# MCU.net
KiCad netlist of a schematic drawn in Altium Designer
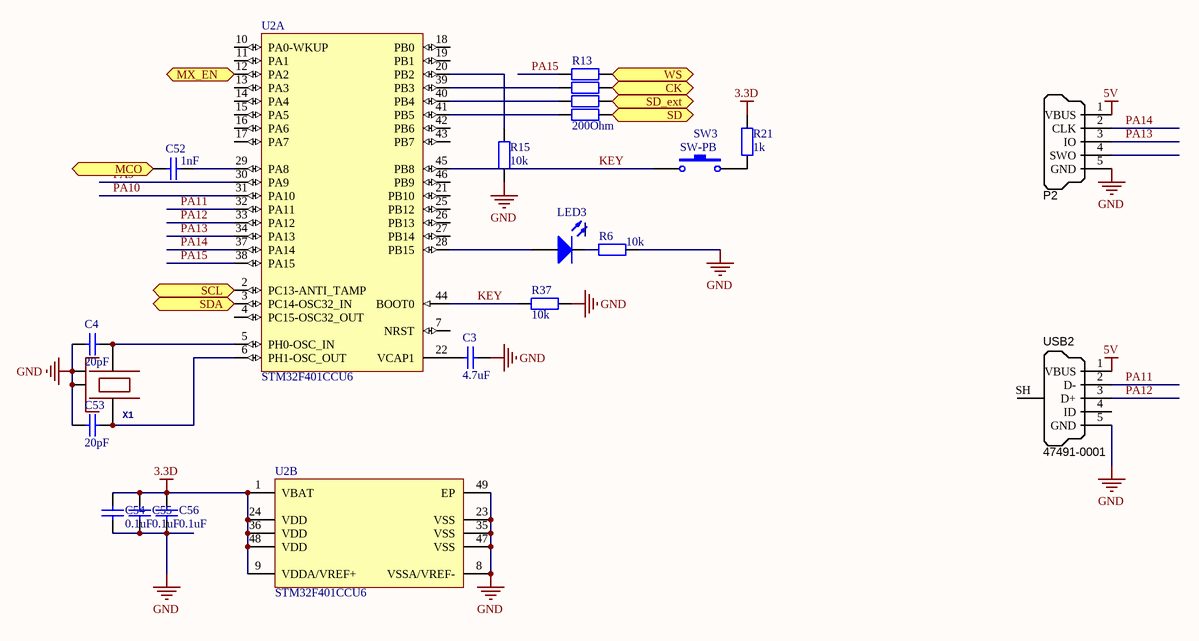
[diagram p0: MCU.SchDoc]

(export (version "E")
  (design (tool "Eeschema 10.0.6"))
  (components
    (comp (ref "C3")
      (value "4.7uF")
      (footprint "0603L")
      (description "Capacitor")
      (fields (field (name "Comment") "Cap") (field (name "PUBLISHER") "Altium Limited"))
      (libsource (lib "RTC6705") (part "Cap"))
    )
    (comp (ref "C4")
      (value "20pF")
      (footprint "0402")
      (description "Capacitor")
      (fields (field (name "Comment") "Cap") (field (name "PUBLISHER") "Altium Limited"))
      (libsource (lib "RTC6705") (part "Cap"))
    )
    (comp (ref "C52")
      (value "1nF")
      (footprint "0402")
      (description "Capacitor")
      (libsource (lib "RTC6705") (part "Cap"))
    )
    (comp (ref "C53")
      (value "20pF")
      (footprint "0402")
      (description "Capacitor")
      (fields (field (name "Comment") "Cap") (field (name "PUBLISHER") "Altium Limited"))
      (libsource (lib "RTC6705") (part "Cap"))
    )
    (comp (ref "C54")
      (value "0.1uF")
      (footprint "0402")
      (description "Capacitor")
      (fields (field (name "Comment") "Cap") (field (name "PUBLISHER") "Altium Limited"))
      (libsource (lib "RTC6705") (part "Cap"))
    )
    (comp (ref "C55")
      (value "0.1uF")
      (footprint "0402")
      (description "Capacitor")
      (fields (field (name "Comment") "Cap") (field (name "PUBLISHER") "Altium Limited"))
      (libsource (lib "RTC6705") (part "Cap"))
    )
    (comp (ref "C56")
      (value "0.1uF")
      (footprint "0402")
      (description "Capacitor")
      (fields (field (name "Comment") "Cap") (field (name "PUBLISHER") "Altium Limited"))
      (libsource (lib "RTC6705") (part "Cap"))
    )
    (comp (ref "LED3")
      (value "LED0")
      (footprint "0603")
      (description "Typical INFRARED GaAs LED")
      (fields (field (name "PUBLISHER") "Altium Limited"))
      (libsource (lib "Miscellaneous Devices") (part "LED0"))
    )
    (comp (ref "P2")
      (value "SWD_MicroUSB")
      (footprint "MICRO-YZX")
      (description "Connector SMD USB Micro Type B middle mount")
      (libsource (lib "sch") (part "SWD_MicroUSB"))
    )
    (comp (ref "R6")
      (value "10k")
      (footprint "0402")
      (description "Resistor")
      (fields (field (name "PUBLISHER") "Altium Limited"))
      (libsource (lib "") (part "Res2_2"))
    )
    (comp (ref "R13")
      (value "200Ohm")
      (footprint "0402X4")
      (description "Resistor")
      (fields (field (name "Comment") "Res*4") (field (name "PUBLISHER") "Altium Limited"))
      (libsource (lib "sch") (part "Res*4"))
    )
    (comp (ref "R15")
      (value "10k")
      (footprint "0402")
      (description "Resistor")
      (fields (field (name "PUBLISHER") "Altium Limited"))
      (libsource (lib "") (part "Res2_1"))
    )
    (comp (ref "R21")
      (value "1k")
      (footprint "0402")
      (description "Resistor")
      (fields (field (name "PUBLISHER") "Altium Limited"))
      (libsource (lib "Miscellaneous Devices") (part "Res2"))
    )
    (comp (ref "R37")
      (value "10k")
      (footprint "0402")
      (description "Resistor")
      (fields (field (name "Comment") "Res2") (field (name "PUBLISHER") "Altium Limited"))
      (libsource (lib "RTC6705") (part "Res2"))
    )
    (comp (ref "SW3")
      (value "SW-PB")
      (footprint "SW3x4")
      (description "Switch")
      (fields (field (name "PUBLISHER") "Altium Limited"))
      (libsource (lib "Miscellaneous Devices") (part "SW-PB"))
    )
    (comp (ref "U2")
      (value "STM32F401CCU6")
      (footprint "STM-UFQFPN48_N")
      (fields (field (name "MANUFACTURER") "STMicroelectronics"))
      (libsource (lib "STMicroelectronics STM32 F4") (part "STM32F401CCU6"))
    )
    (comp (ref "USB2")
      (value "USB Micro Type B")
      (footprint "MICRO-YZX")
      (description "Connector SMD USB Micro Type B middle mount")
      (fields (field (name "MANUFACTURER PART NUMBER 1") "47491-0001"))
      (libsource (lib "PBL - Connectors") (part "USB_Micro_TypeB"))
    )
    (comp (ref "X1")
      (value "24.000 KHz 3.2x2.5mm 8-10pf")
      (footprint "OSCILLATOR-2.5x2.0")
      (description "Crystal Oscillator in 3.2x2.5 SMD")
      (libsource (lib "pixhawk2") (part "OSCILLATOR-3.2X2.5"))
    )
  )
  (nets
    (net (code "1") (name "/CK") (class "Default")
      (node (ref "R13") (pin "2") (pinfunction "2_2") (pintype "passive"))
    )
    (net (code "2") (name "/KEY") (class "Default")
      (node (ref "R37") (pin "1") (pinfunction "1_1") (pintype "passive"))
      (node (ref "SW3") (pin "1") (pinfunction "1_1") (pintype "passive"))
      (node (ref "U2") (pin "44") (pinfunction "BOOT0_44") (pintype "input"))
      (node (ref "U2") (pin "45") (pinfunction "PB8_45") (pintype "bidirectional"))
    )
    (net (code "3") (name "/MCO") (class "Default")
      (node (ref "C52") (pin "1") (pinfunction "1_1") (pintype "passive"))
    )
    (net (code "4") (name "/MX_EN") (class "Default")
      (node (ref "U2") (pin "12") (pinfunction "PA2_12") (pintype "bidirectional"))
    )
    (net (code "5") (name "/PA9") (class "Default")
      (node (ref "U2") (pin "30") (pinfunction "PA9_30") (pintype "bidirectional"))
    )
    (net (code "6") (name "/PA10") (class "Default")
      (node (ref "U2") (pin "31") (pinfunction "PA10_31") (pintype "bidirectional"))
    )
    (net (code "7") (name "/PA11") (class "Default")
      (node (ref "U2") (pin "32") (pinfunction "PA11_32") (pintype "bidirectional"))
      (node (ref "USB2") (pin "2") (pinfunction "D-_2") (pintype "passive"))
    )
    (net (code "8") (name "/PA12") (class "Default")
      (node (ref "U2") (pin "33") (pinfunction "PA12_33") (pintype "bidirectional"))
      (node (ref "USB2") (pin "3") (pinfunction "D+_3") (pintype "passive"))
    )
    (net (code "9") (name "/PA13") (class "Default")
      (node (ref "P2") (pin "3") (pinfunction "IO_3") (pintype "passive"))
      (node (ref "U2") (pin "34") (pinfunction "PA13_34") (pintype "bidirectional"))
    )
    (net (code "10") (name "/PA14") (class "Default")
      (node (ref "P2") (pin "2") (pinfunction "CLK_2") (pintype "passive"))
      (node (ref "U2") (pin "37") (pinfunction "PA14_37") (pintype "bidirectional"))
    )
    (net (code "11") (name "/PA15") (class "Default")
      (node (ref "R13") (pin "8") (pinfunction "8_8") (pintype "passive"))
      (node (ref "U2") (pin "38") (pinfunction "PA15_38") (pintype "bidirectional"))
    )
    (net (code "12") (name "/SCL") (class "Default")
      (node (ref "U2") (pin "2") (pinfunction "PC13-ANTI_TAMP_2") (pintype "bidirectional"))
    )
    (net (code "13") (name "/SD") (class "Default")
      (node (ref "R13") (pin "4") (pinfunction "4_4") (pintype "passive"))
    )
    (net (code "14") (name "/SDA") (class "Default")
      (node (ref "U2") (pin "3") (pinfunction "PC14-OSC32_IN_3") (pintype "bidirectional"))
    )
    (net (code "15") (name "/SD_ext") (class "Default")
      (node (ref "R13") (pin "3") (pinfunction "3_3") (pintype "passive"))
    )
    (net (code "16") (name "/WS") (class "Default")
      (node (ref "R13") (pin "1") (pinfunction "1_1") (pintype "passive"))
    )
    (net (code "17") (name "3.3D") (class "Default")
      (node (ref "C54") (pin "2") (pinfunction "2_2") (pintype "passive"))
      (node (ref "C55") (pin "2") (pinfunction "2_2") (pintype "passive"))
      (node (ref "C56") (pin "2") (pinfunction "2_2") (pintype "passive"))
      (node (ref "R21") (pin "2") (pinfunction "2_2") (pintype "passive"))
      (node (ref "U2") (pin "1") (pinfunction "VBAT_1") (pintype "power_in"))
      (node (ref "U2") (pin "24") (pinfunction "VDD_24") (pintype "power_in"))
      (node (ref "U2") (pin "36") (pinfunction "VDD_36") (pintype "power_in"))
      (node (ref "U2") (pin "48") (pinfunction "VDD_48") (pintype "power_in"))
      (node (ref "U2") (pin "9") (pinfunction "VDDA/VREF+_9") (pintype "power_in"))
    )
    (net (code "18") (name "5V") (class "Default")
      (node (ref "P2") (pin "1") (pinfunction "VBUS_1") (pintype "passive"))
      (node (ref "USB2") (pin "1") (pinfunction "VBUS_1") (pintype "passive"))
    )
    (net (code "19") (name "GND") (class "Default")
      (node (ref "C3") (pin "1") (pinfunction "1_1") (pintype "passive"))
      (node (ref "C4") (pin "1") (pinfunction "1_1") (pintype "passive"))
      (node (ref "C53") (pin "1") (pinfunction "1_1") (pintype "passive"))
      (node (ref "C54") (pin "1") (pinfunction "1_1") (pintype "passive"))
      (node (ref "C55") (pin "1") (pinfunction "1_1") (pintype "passive"))
      (node (ref "C56") (pin "1") (pinfunction "1_1") (pintype "passive"))
      (node (ref "P2") (pin "5") (pinfunction "GND_5") (pintype "passive"))
      (node (ref "R15") (pin "2") (pinfunction "2_2") (pintype "passive"))
      (node (ref "R37") (pin "2") (pinfunction "2_2") (pintype "passive"))
      (node (ref "R6") (pin "2") (pinfunction "2_2") (pintype "passive"))
      (node (ref "U2") (pin "23") (pinfunction "VSS_23") (pintype "power_in"))
      (node (ref "U2") (pin "35") (pinfunction "VSS_35") (pintype "power_in"))
      (node (ref "U2") (pin "47") (pinfunction "VSS_47") (pintype "power_in"))
      (node (ref "U2") (pin "49") (pinfunction "EP_49") (pintype "power_in"))
      (node (ref "U2") (pin "8") (pinfunction "VSSA/VREF-_8") (pintype "power_in"))
      (node (ref "USB2") (pin "5") (pinfunction "GND_5") (pintype "passive"))
      (node (ref "X1") (pin "2") (pinfunction "NC_2_2") (pintype "open_emitter"))
      (node (ref "X1") (pin "4") (pinfunction "NC_4_4") (pintype "open_emitter"))
    )
    (net (code "20") (name "Net-(LED3-A)") (class "Default")
      (node (ref "LED3") (pin "1") (pinfunction "A_1") (pintype "passive"))
      (node (ref "U2") (pin "28") (pinfunction "PB15_28") (pintype "bidirectional"))
    )
    (net (code "21") (name "Net-(LED3-K)") (class "Default")
      (node (ref "LED3") (pin "2") (pinfunction "K_2") (pintype "passive"))
      (node (ref "R6") (pin "1") (pinfunction "1_1") (pintype "passive"))
    )
    (net (code "22") (name "Net-(R21-Pad1)") (class "Default")
      (node (ref "R21") (pin "1") (pinfunction "1_1") (pintype "passive"))
      (node (ref "SW3") (pin "2") (pinfunction "2_2") (pintype "passive"))
    )
    (net (code "23") (name "Net-(U2A-PA8)") (class "Default")
      (node (ref "C52") (pin "2") (pinfunction "2_2") (pintype "passive"))
      (node (ref "U2") (pin "29") (pinfunction "PA8_29") (pintype "bidirectional"))
    )
    (net (code "24") (name "Net-(U2A-PB2)") (class "Default")
      (node (ref "R15") (pin "1") (pinfunction "1_1") (pintype "passive"))
      (node (ref "U2") (pin "20") (pinfunction "PB2_20") (pintype "bidirectional"))
    )
    (net (code "25") (name "Net-(U2A-PB3)") (class "Default")
      (node (ref "R13") (pin "7") (pinfunction "7_7") (pintype "passive"))
      (node (ref "U2") (pin "39") (pinfunction "PB3_39") (pintype "bidirectional"))
    )
    (net (code "26") (name "Net-(U2A-PB4)") (class "Default")
      (node (ref "R13") (pin "6") (pinfunction "6_6") (pintype "passive"))
      (node (ref "U2") (pin "40") (pinfunction "PB4_40") (pintype "bidirectional"))
    )
    (net (code "27") (name "Net-(U2A-PB5)") (class "Default")
      (node (ref "R13") (pin "5") (pinfunction "5_5") (pintype "passive"))
      (node (ref "U2") (pin "41") (pinfunction "PB5_41") (pintype "bidirectional"))
    )
    (net (code "28") (name "Net-(U2A-PH0-OSC_IN)") (class "Default")
      (node (ref "C4") (pin "2") (pinfunction "2_2") (pintype "passive"))
      (node (ref "U2") (pin "5") (pinfunction "PH0-OSC_IN_5") (pintype "bidirectional"))
      (node (ref "X1") (pin "1") (pinfunction "1_1") (pintype "passive"))
    )
    (net (code "29") (name "Net-(U2A-PH1-OSC_OUT)") (class "Default")
      (node (ref "C53") (pin "2") (pinfunction "2_2") (pintype "passive"))
      (node (ref "U2") (pin "6") (pinfunction "PH1-OSC_OUT_6") (pintype "bidirectional"))
      (node (ref "X1") (pin "3") (pinfunction "3_3") (pintype "passive"))
    )
    (net (code "30") (name "Net-(U2A-VCAP1)") (class "Default")
      (node (ref "C3") (pin "2") (pinfunction "2_2") (pintype "passive"))
      (node (ref "U2") (pin "22") (pinfunction "VCAP1_22") (pintype "power_in"))
    )
    (net (code "31") (name "unconnected-(P2-SWO-Pad4)") (class "Default")
      (node (ref "P2") (pin "4") (pinfunction "SWO_4") (pintype "passive"))
    )
    (net (code "32") (name "unconnected-(U2A-NRST-Pad7)") (class "Default")
      (node (ref "U2") (pin "7") (pinfunction "NRST_7") (pintype "bidirectional"))
    )
    (net (code "33") (name "unconnected-(U2A-PA0-WKUP-Pad10)") (class "Default")
      (node (ref "U2") (pin "10") (pinfunction "PA0-WKUP_10") (pintype "bidirectional"))
    )
    (net (code "34") (name "unconnected-(U2A-PA1-Pad11)") (class "Default")
      (node (ref "U2") (pin "11") (pinfunction "PA1_11") (pintype "bidirectional"))
    )
    (net (code "35") (name "unconnected-(U2A-PA3-Pad13)") (class "Default")
      (node (ref "U2") (pin "13") (pinfunction "PA3_13") (pintype "bidirectional"))
    )
    (net (code "36") (name "unconnected-(U2A-PA4-Pad14)") (class "Default")
      (node (ref "U2") (pin "14") (pinfunction "PA4_14") (pintype "bidirectional"))
    )
    (net (code "37") (name "unconnected-(U2A-PA5-Pad15)") (class "Default")
      (node (ref "U2") (pin "15") (pinfunction "PA5_15") (pintype "bidirectional"))
    )
    (net (code "38") (name "unconnected-(U2A-PA6-Pad16)") (class "Default")
      (node (ref "U2") (pin "16") (pinfunction "PA6_16") (pintype "bidirectional"))
    )
    (net (code "39") (name "unconnected-(U2A-PA7-Pad17)") (class "Default")
      (node (ref "U2") (pin "17") (pinfunction "PA7_17") (pintype "bidirectional"))
    )
    (net (code "40") (name "unconnected-(U2A-PB0-Pad18)") (class "Default")
      (node (ref "U2") (pin "18") (pinfunction "PB0_18") (pintype "bidirectional"))
    )
    (net (code "41") (name "unconnected-(U2A-PB1-Pad19)") (class "Default")
      (node (ref "U2") (pin "19") (pinfunction "PB1_19") (pintype "bidirectional"))
    )
    (net (code "42") (name "unconnected-(U2A-PB6-Pad42)") (class "Default")
      (node (ref "U2") (pin "42") (pinfunction "PB6_42") (pintype "bidirectional"))
    )
    (net (code "43") (name "unconnected-(U2A-PB7-Pad43)") (class "Default")
      (node (ref "U2") (pin "43") (pinfunction "PB7_43") (pintype "bidirectional"))
    )
    (net (code "44") (name "unconnected-(U2A-PB9-Pad46)") (class "Default")
      (node (ref "U2") (pin "46") (pinfunction "PB9_46") (pintype "bidirectional"))
    )
    (net (code "45") (name "unconnected-(U2A-PB10-Pad21)") (class "Default")
      (node (ref "U2") (pin "21") (pinfunction "PB10_21") (pintype "bidirectional"))
    )
    (net (code "46") (name "unconnected-(U2A-PB12-Pad25)") (class "Default")
      (node (ref "U2") (pin "25") (pinfunction "PB12_25") (pintype "bidirectional"))
    )
    (net (code "47") (name "unconnected-(U2A-PB13-Pad26)") (class "Default")
      (node (ref "U2") (pin "26") (pinfunction "PB13_26") (pintype "bidirectional"))
    )
    (net (code "48") (name "unconnected-(U2A-PB14-Pad27)") (class "Default")
      (node (ref "U2") (pin "27") (pinfunction "PB14_27") (pintype "bidirectional"))
    )
    (net (code "49") (name "unconnected-(U2A-PC15-OSC32_OUT-Pad4)") (class "Default")
      (node (ref "U2") (pin "4") (pinfunction "PC15-OSC32_OUT_4") (pintype "bidirectional"))
    )
    (net (code "50") (name "unconnected-(USB2-ID-Pad4)") (class "Default")
      (node (ref "USB2") (pin "4") (pinfunction "ID_4") (pintype "passive"))
    )
    (net (code "51") (name "unconnected-(USB2-Shell-PadSH)") (class "Default")
      (node (ref "USB2") (pin "SH") (pinfunction "Shell_SH") (pintype "passive"))
    )
  )
)
